# 0113_AUDIO_-_SNDW2_for.net
KiCad netlist of a schematic drawn in Altium Designer
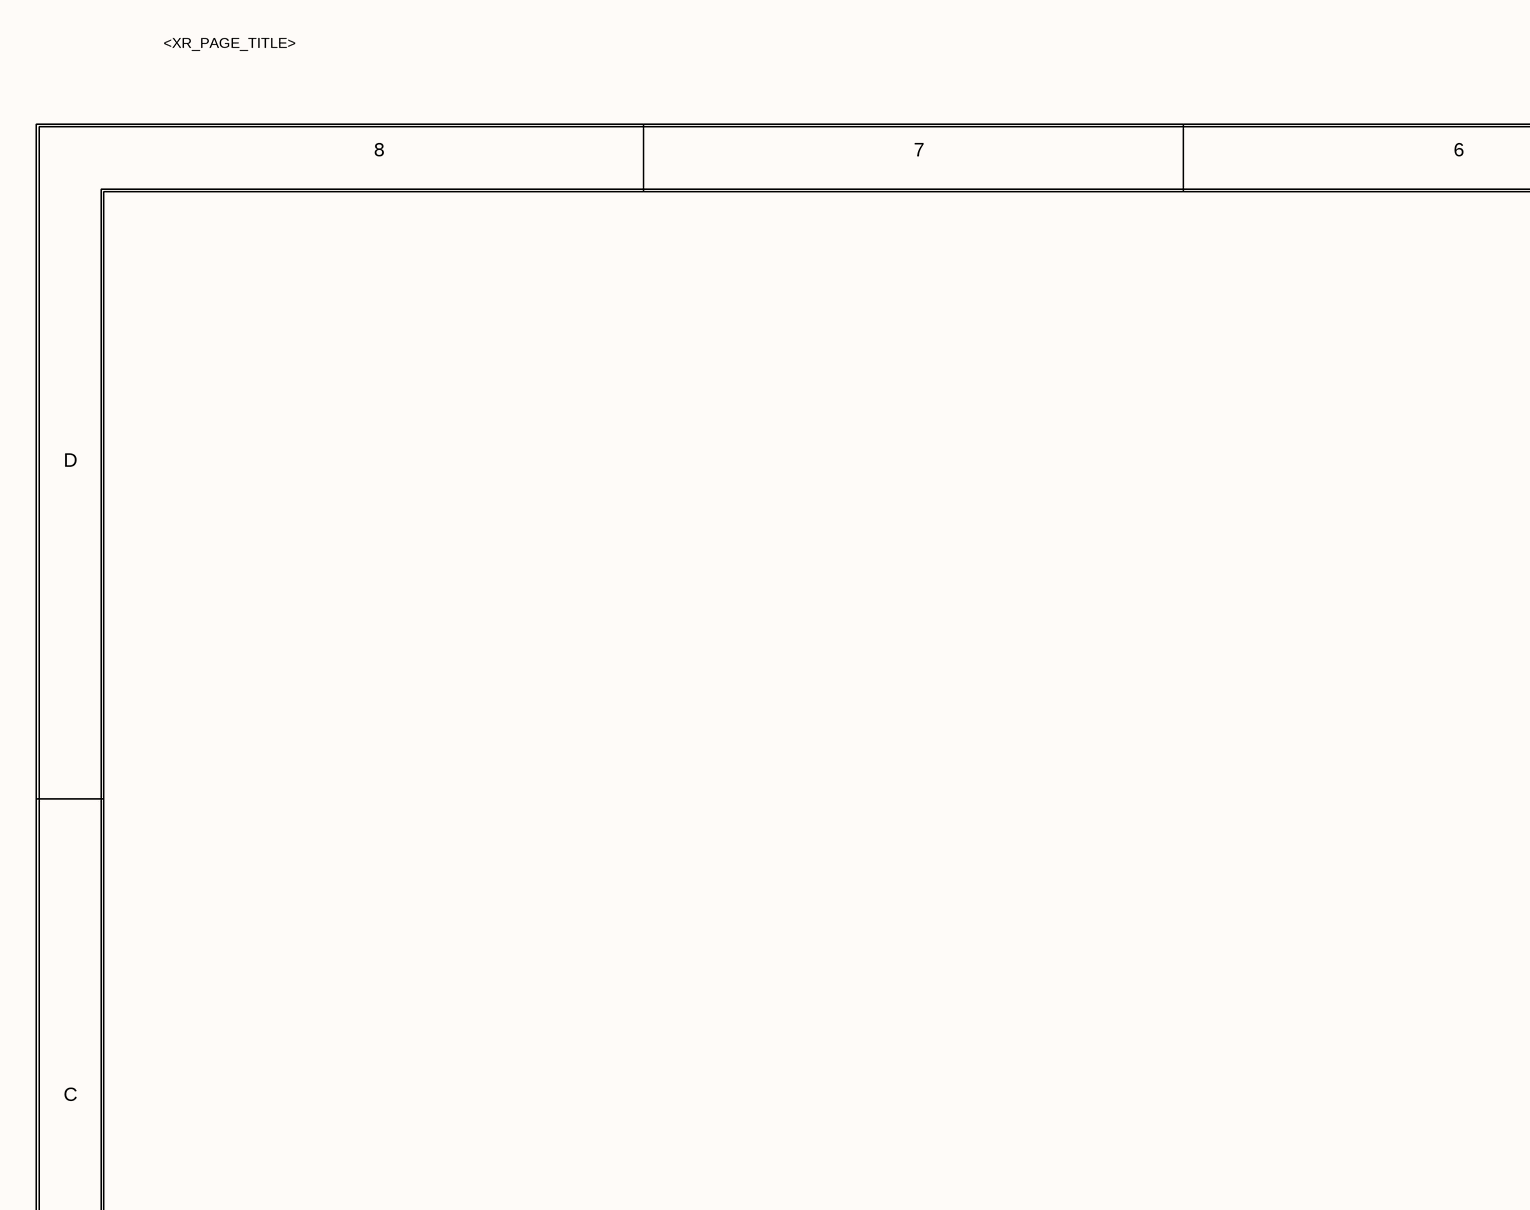
[diagram p0: 0113_AUDIO - SNDW2 for .SchDoc, top left]
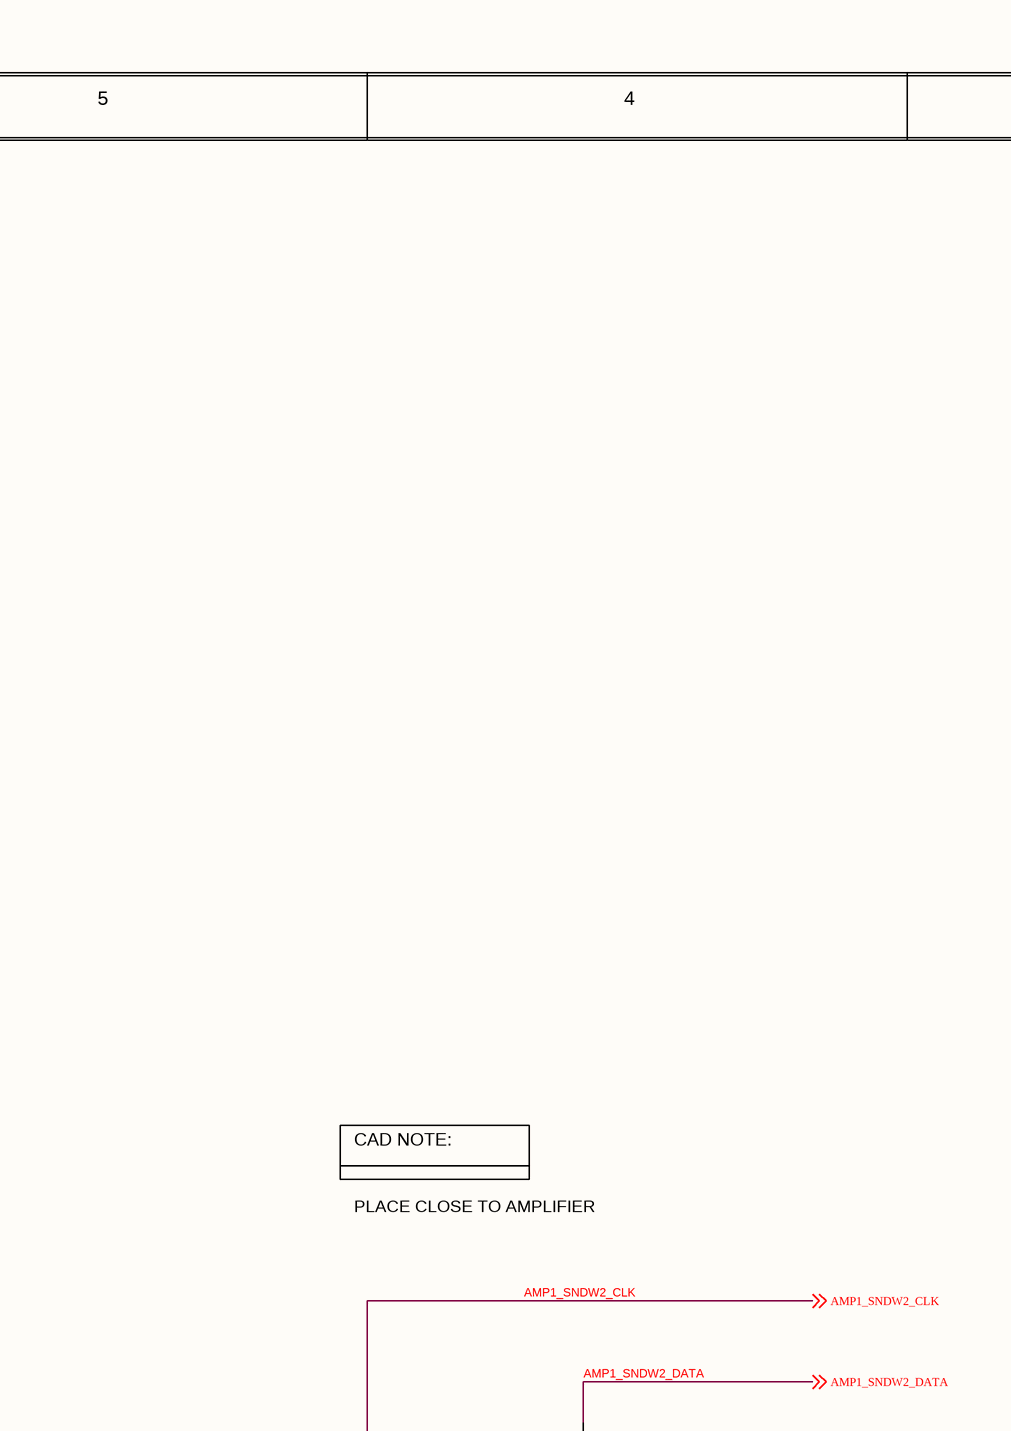
[diagram p1: 0113_AUDIO - SNDW2 for .SchDoc, top middle]
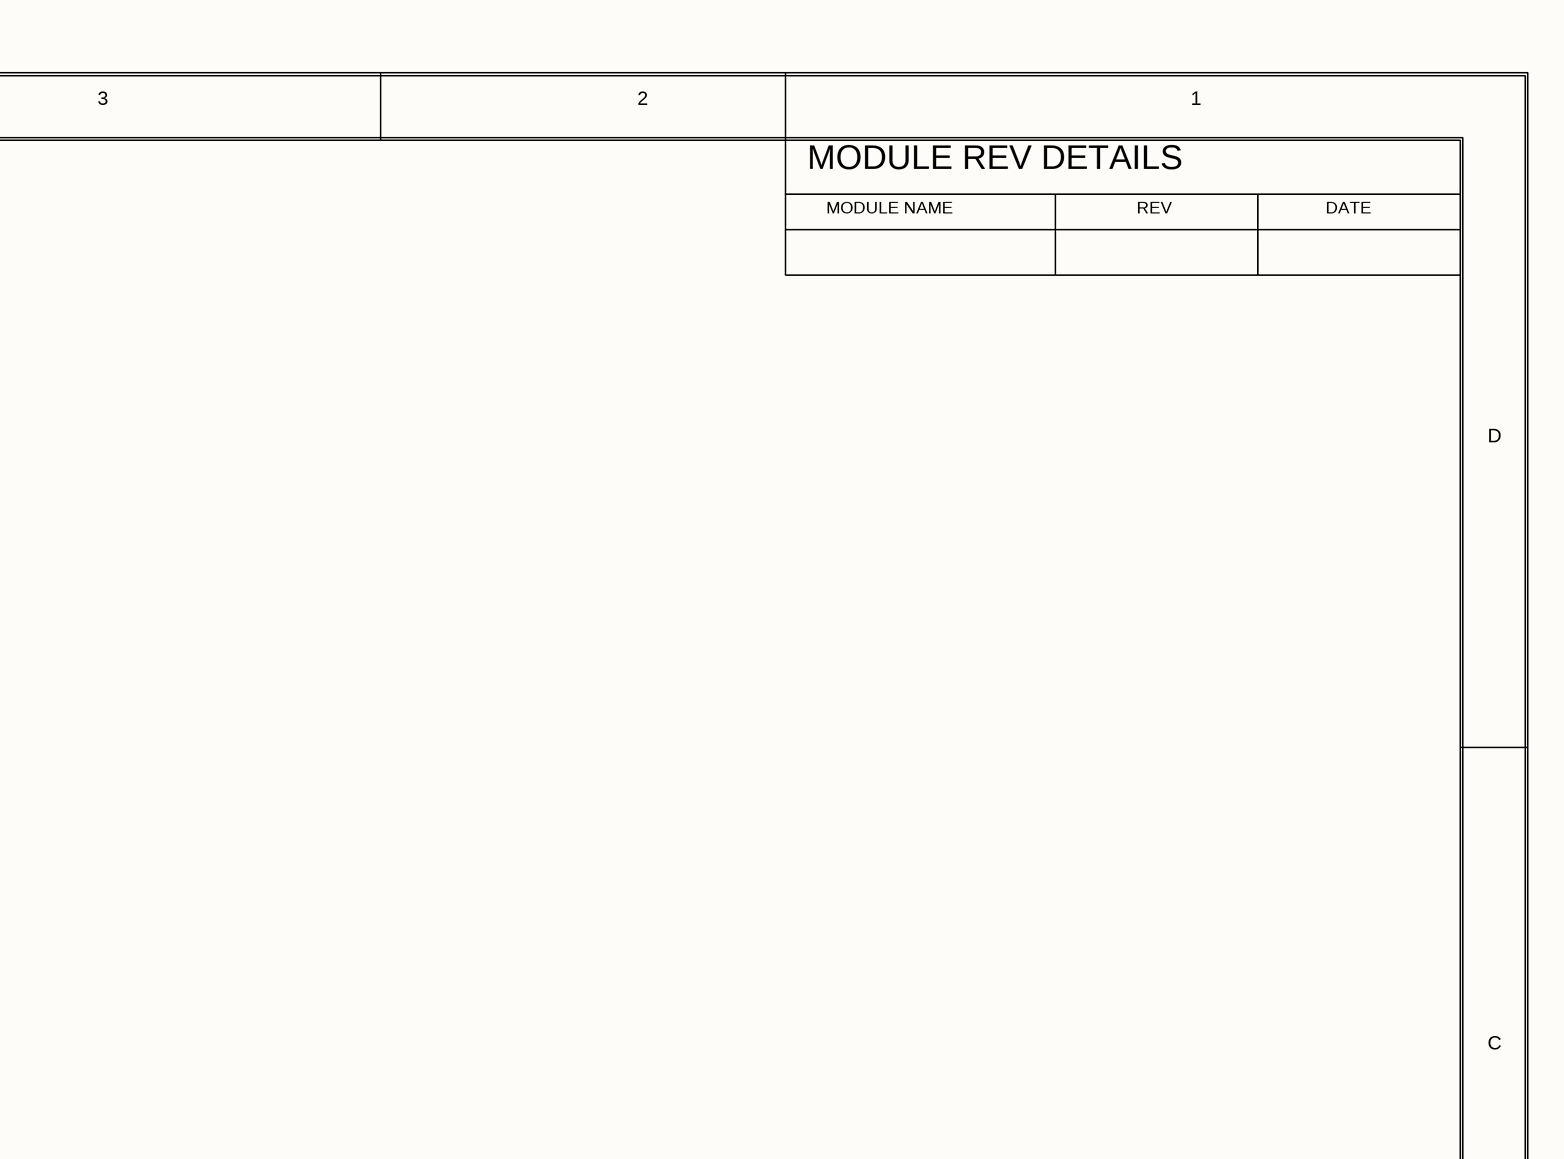
[diagram p2: 0113_AUDIO - SNDW2 for .SchDoc, top right]
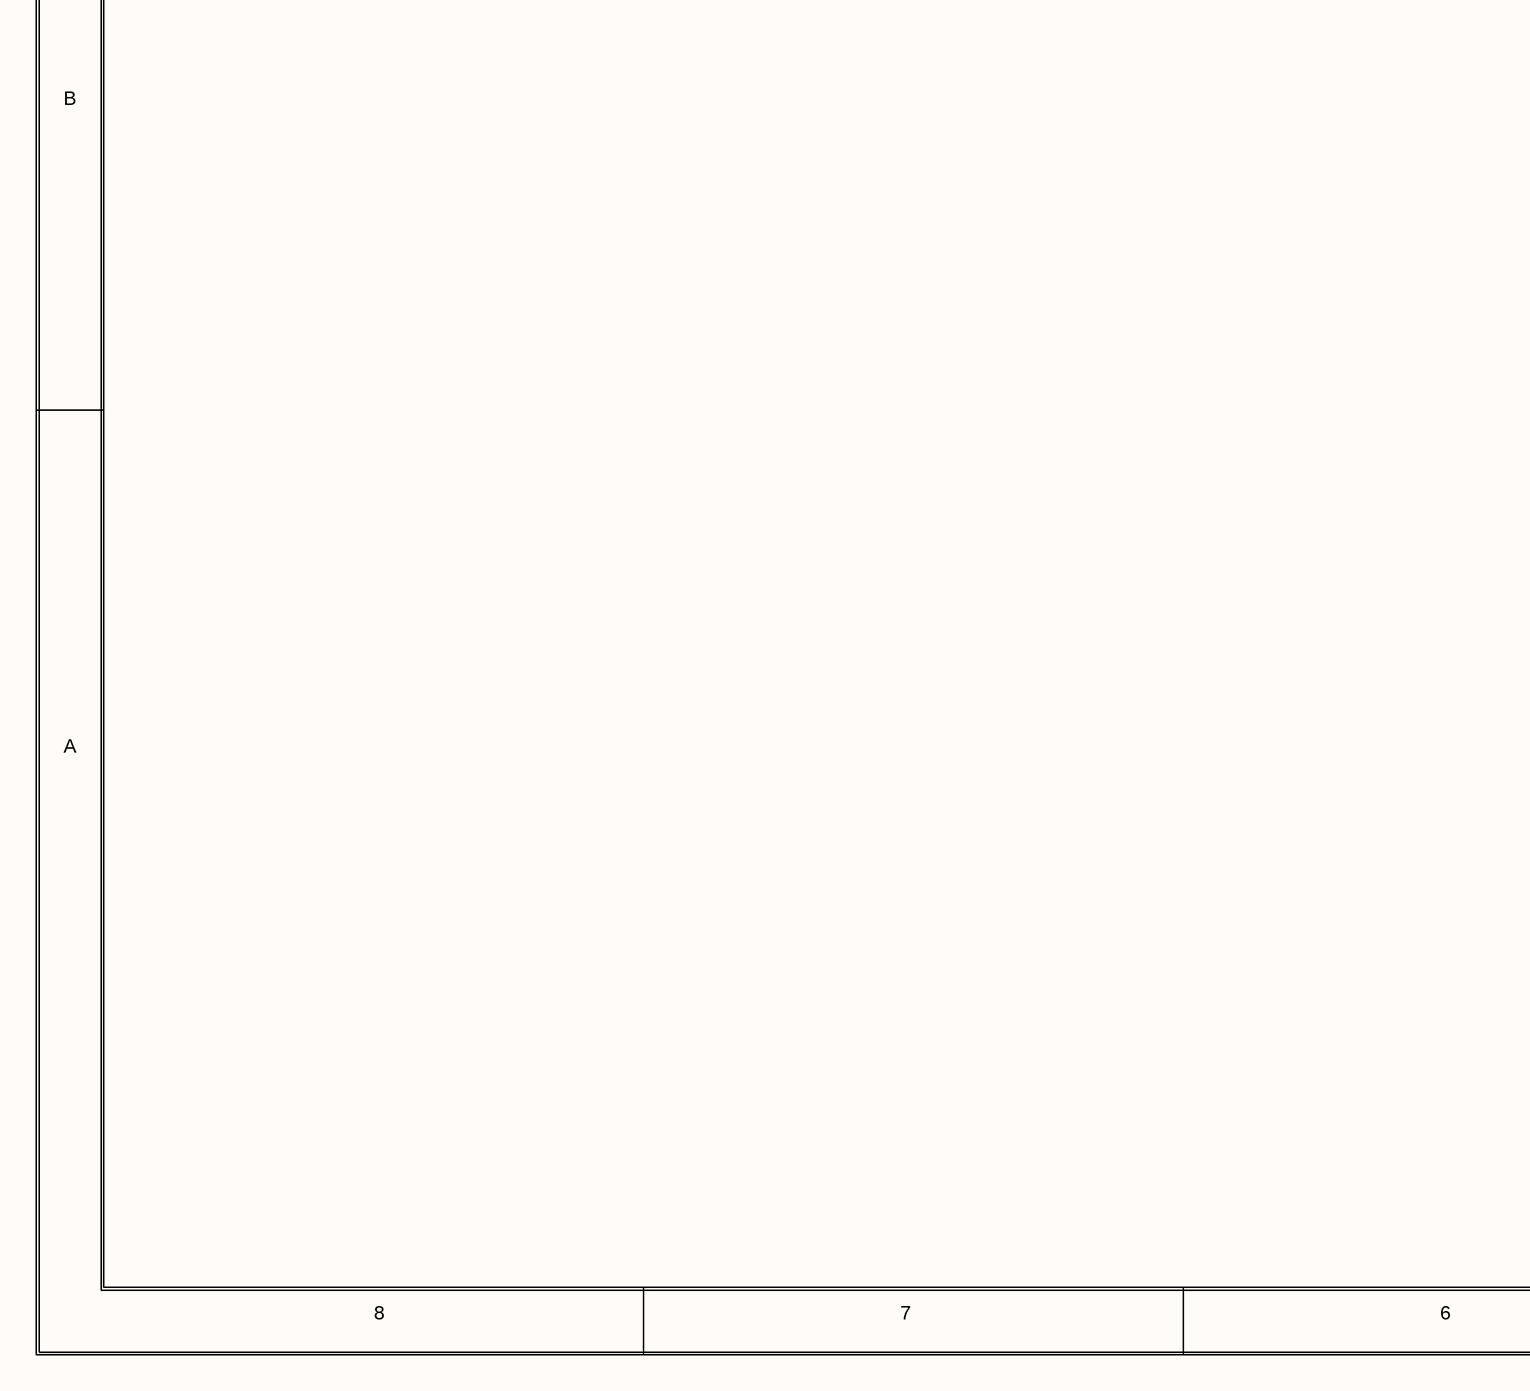
[diagram p3: 0113_AUDIO - SNDW2 for .SchDoc, bottom left]
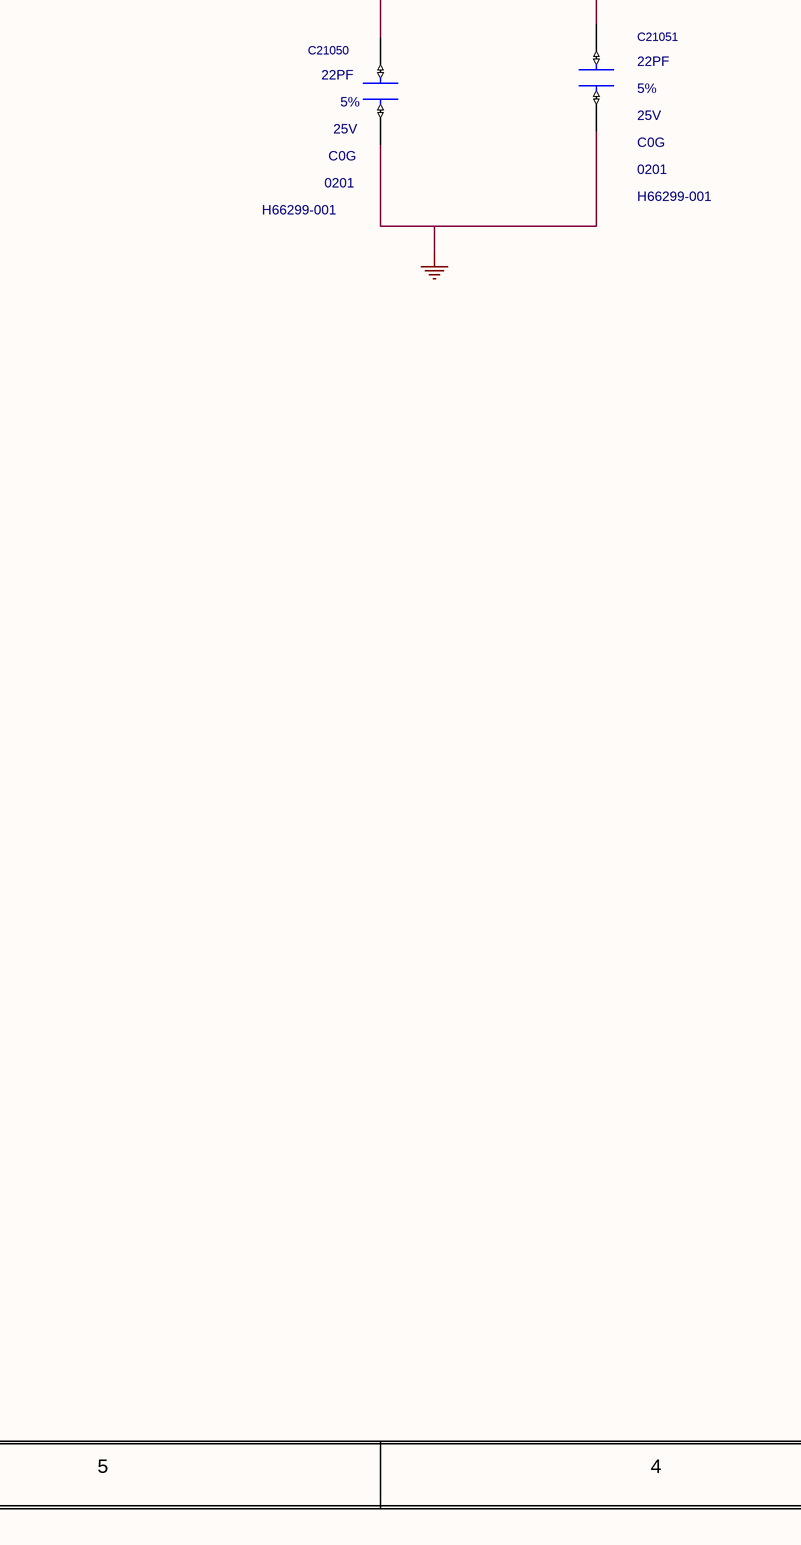
[diagram p4: 0113_AUDIO - SNDW2 for .SchDoc, bottom middle]
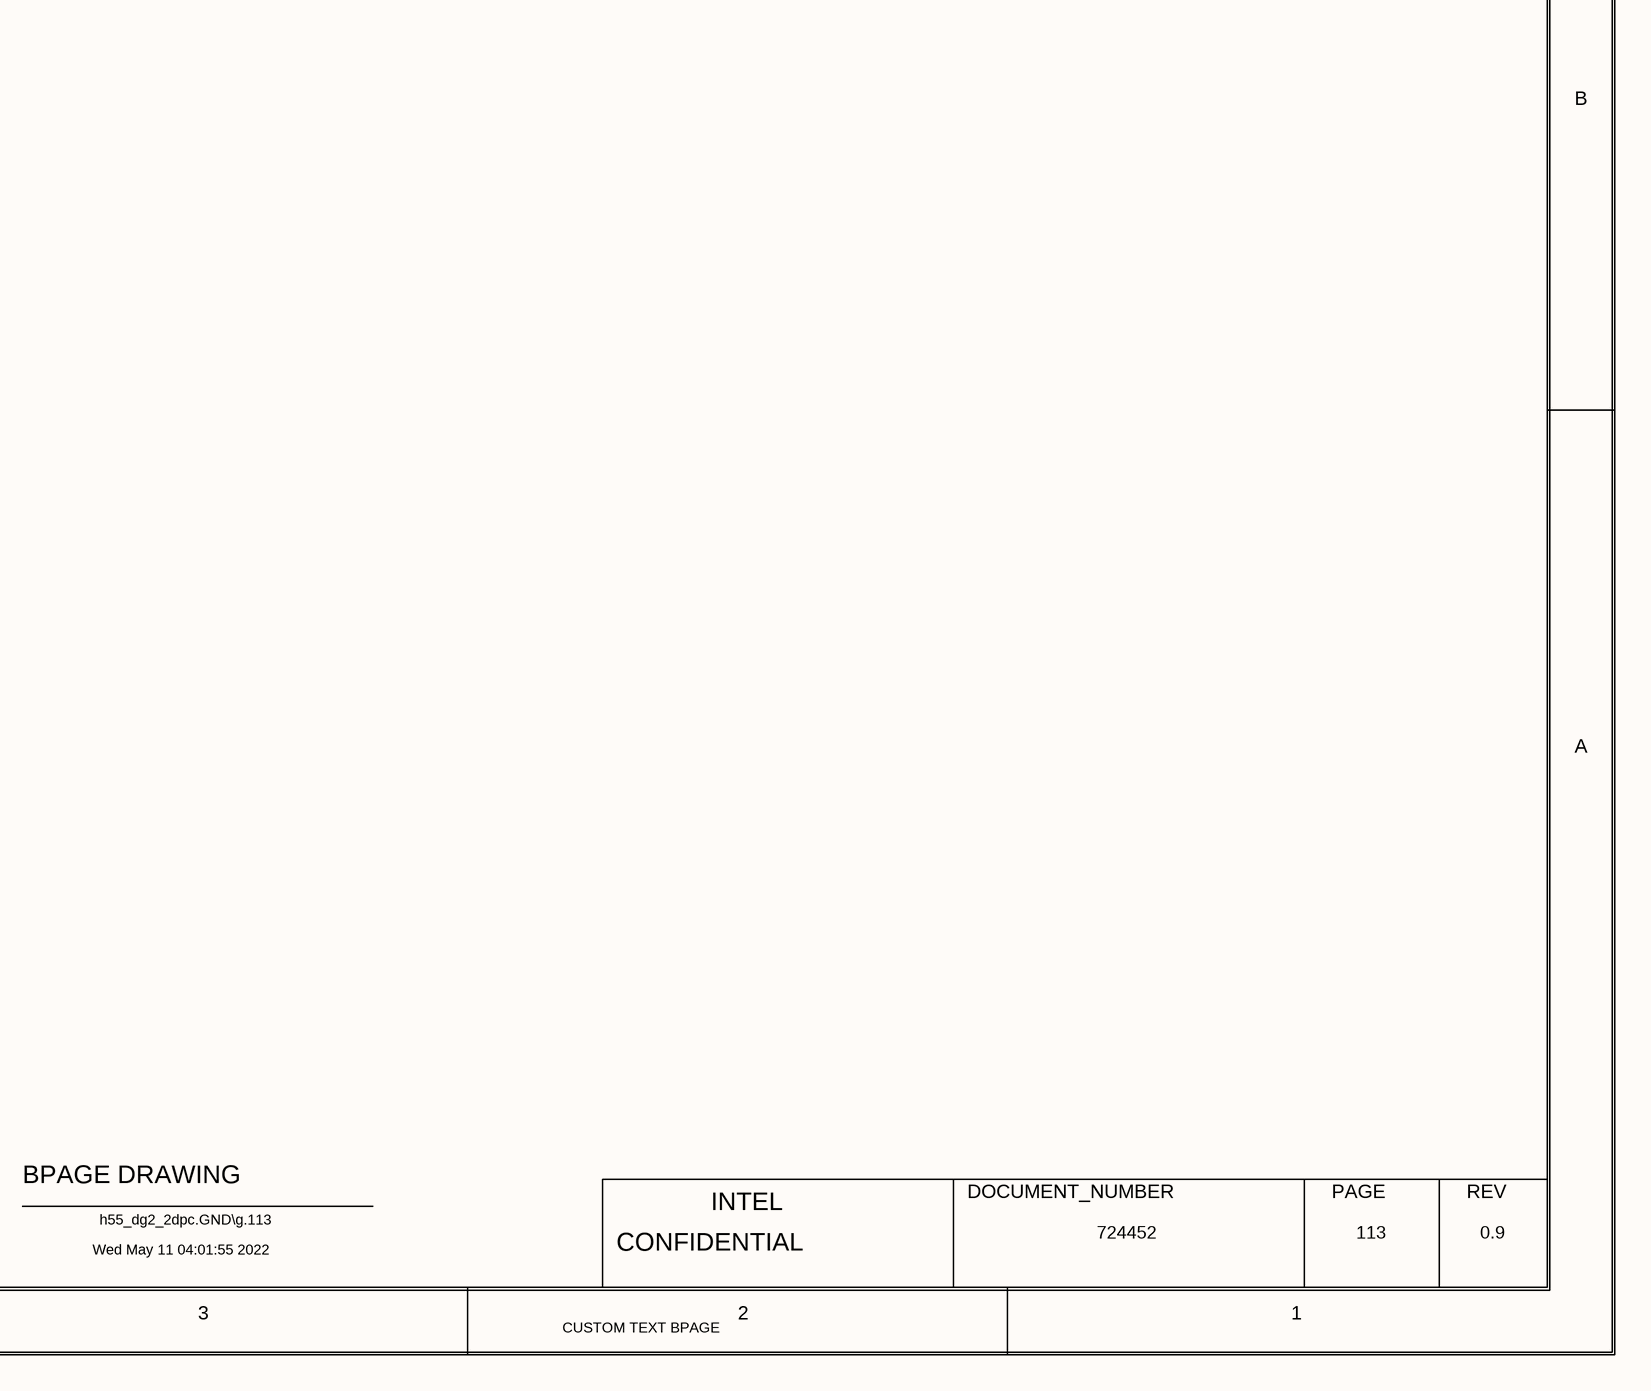
[diagram p5: 0113_AUDIO - SNDW2 for .SchDoc, bottom right]

(export (version "E")
  (design (tool "Eeschema 10.0.6"))
  (components
    (comp (ref "C21050")
      (value "22PF")
      (footprint "CTK0_SM0201_630X330_MA")
      (fields
        (field (name "MATERIAL") "C0G")
        (field (name "PACK_TYPE") "0201")
        (field (name "PART_NUMBER") "H66299-001")
        (field (name "TOLERANCE") "5%")
        (field (name "VOLTAGE") "25V")
      )
      (libsource (lib "*") (part "C_CAP"))
    )
    (comp (ref "C21051")
      (value "22PF")
      (footprint "CTK0_SM0201_630X330_MA")
      (fields
        (field (name "MATERIAL") "C0G")
        (field (name "PACK_TYPE") "0201")
        (field (name "PART_NUMBER") "H66299-001")
        (field (name "TOLERANCE") "5%")
        (field (name "VOLTAGE") "25V")
      )
      (libsource (lib "*") (part "C_CAP"))
    )
  )
  (nets
    (net (code "1") (name "AMP1_SNDW2_CLK") (class "Default")
      (node (ref "C21050") (pin "1") (pinfunction "A_1") (pintype "bidirectional"))
    )
    (net (code "2") (name "AMP1_SNDW2_DATA") (class "Default")
      (node (ref "C21051") (pin "1") (pinfunction "A_1") (pintype "bidirectional"))
    )
    (net (code "4") (name "GND") (class "Default")
      (node (ref "C21050") (pin "2") (pinfunction "B_2") (pintype "bidirectional"))
      (node (ref "C21051") (pin "2") (pinfunction "B_2") (pintype "bidirectional"))
    )
  )
)
